# rs485.net
KiCad netlist of a schematic drawn in Altium Designer
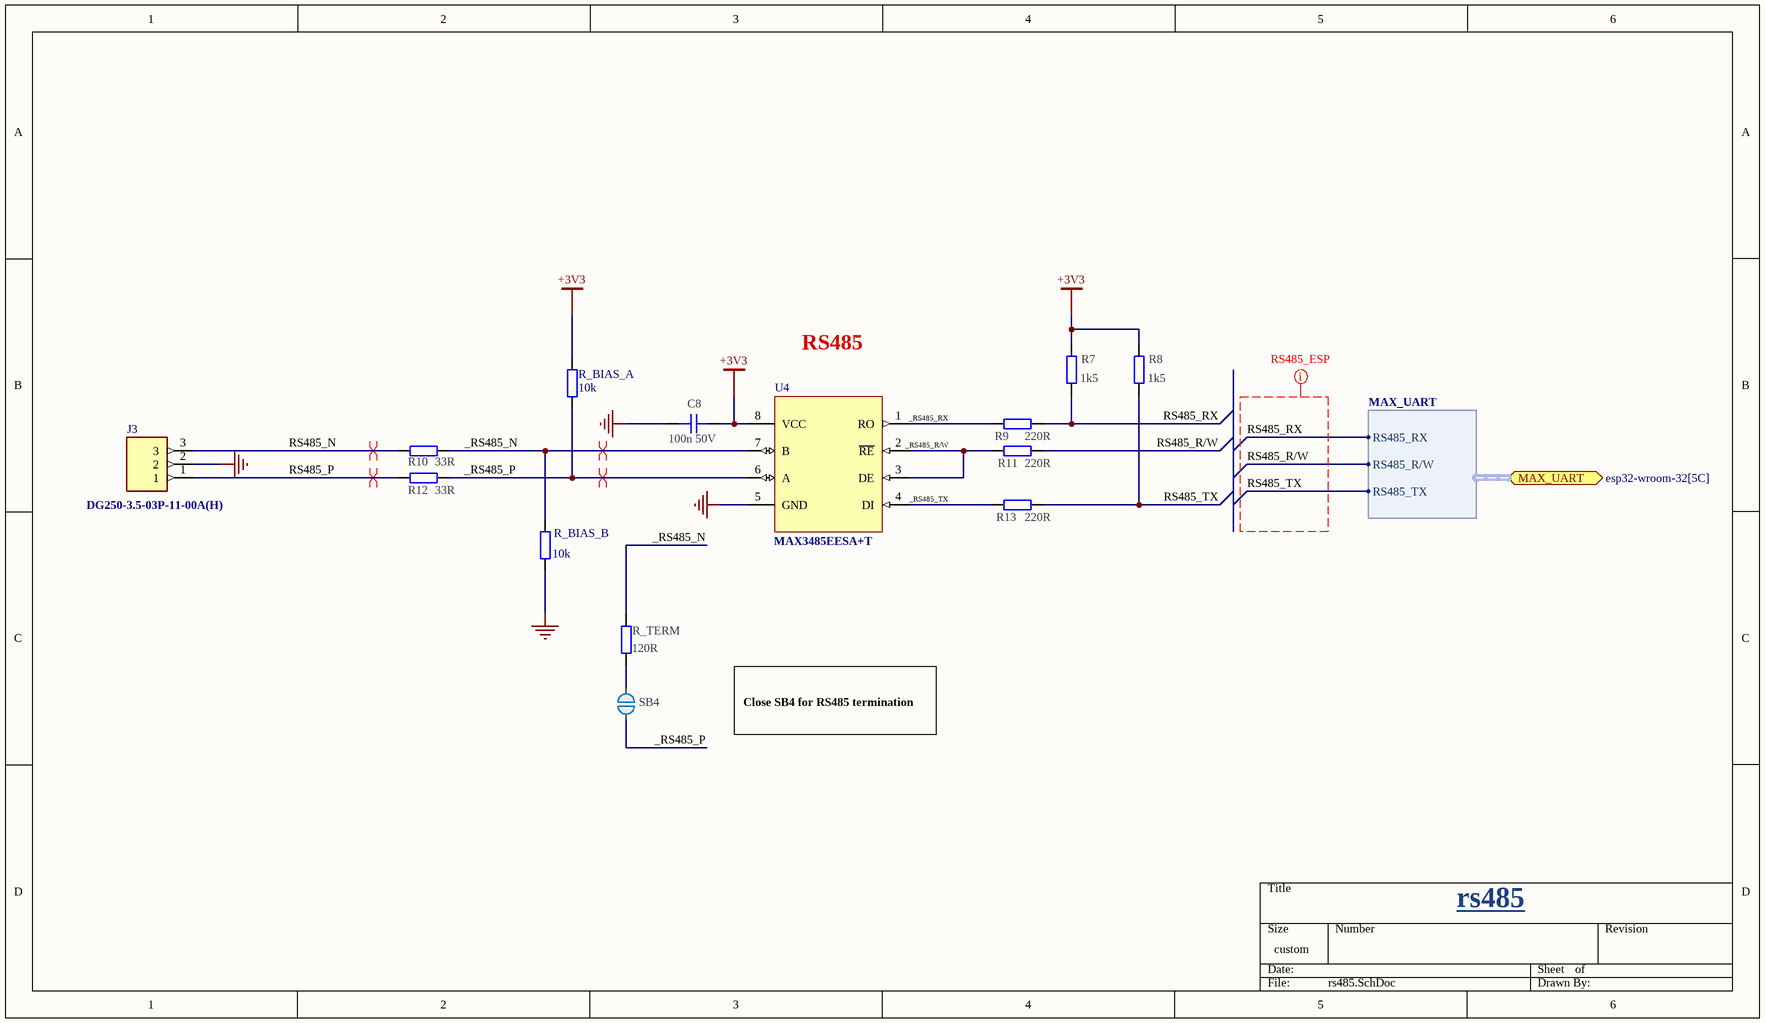
[diagram p0: rs485.SchDoc]

(export (version "E")
  (design (tool "Eeschema 10.0.6"))
  (components
    (comp (ref "C8")
      (value "100n 50V")
      (footprint "CAPC1005X04L")
      (description "Capacitor, X5R, ±20%")
      (fields
        (field (name "PART NUMBER") "C0402-4µ7")
        (field (name "MANUFACTURER") "N.A.")
        (field (name "AUTHOR") "rsk")
      )
      (libsource (lib "Sch_Lib") (part "C0402-4µ7"))
    )
    (comp (ref "J3")
      (value "DG250-3.5-03P-11-00A(H)")
      (footprint "DG250-3.5-03P-11-00AH")
      (description "Terminal block; 3.5mm; with push button; angled 45Â°; ways: 3; 5A")
      (fields (field (name "MF") "Degson"))
      (libsource (lib "Sch_Lib") (part "DG250-3.5-03P-11-00A(H)"))
    )
    (comp (ref "R7")
      (value "1k5")
      (footprint "RESC1005X04L")
      (description "Resistor, ±5%, 0.063W")
      (fields
        (field (name "PART NUMBER") "R0402-0R")
        (field (name "MANUFACTURER") "N.A.")
        (field (name "AUTHOR") "rsk")
      )
      (libsource (lib "Sch_Lib") (part "R0402-0R"))
    )
    (comp (ref "R8")
      (value "1k5")
      (footprint "RESC1005X04L")
      (description "Resistor, ±5%, 0.063W")
      (fields
        (field (name "PART NUMBER") "R0402-0R")
        (field (name "MANUFACTURER") "N.A.")
        (field (name "AUTHOR") "rsk")
      )
      (libsource (lib "Sch_Lib") (part "R0402-0R"))
    )
    (comp (ref "R9")
      (value "220R")
      (footprint "RESC1005X04L")
      (description "Resistor, ±5%, 0.063W")
      (fields
        (field (name "PART NUMBER") "R0402-0R")
        (field (name "MANUFACTURER") "N.A.")
        (field (name "AUTHOR") "rsk")
      )
      (libsource (lib "Sch_Lib") (part "R0402-0R"))
    )
    (comp (ref "R10")
      (value "33R")
      (footprint "RESC1005X04L")
      (description "Resistor, ±5%, 0.063W")
      (fields
        (field (name "PART NUMBER") "R0402-0R")
        (field (name "MANUFACTURER") "N.A.")
        (field (name "AUTHOR") "rsk")
      )
      (libsource (lib "Sch_Lib") (part "R0402-0R"))
    )
    (comp (ref "R11")
      (value "220R")
      (footprint "RESC1005X04L")
      (description "Resistor, ±5%, 0.063W")
      (fields
        (field (name "PART NUMBER") "R0402-0R")
        (field (name "MANUFACTURER") "N.A.")
        (field (name "AUTHOR") "rsk")
      )
      (libsource (lib "Sch_Lib") (part "R0402-0R"))
    )
    (comp (ref "R12")
      (value "33R")
      (footprint "RESC1005X04L")
      (description "Resistor, ±5%, 0.063W")
      (fields
        (field (name "PART NUMBER") "R0402-0R")
        (field (name "MANUFACTURER") "N.A.")
        (field (name "AUTHOR") "rsk")
      )
      (libsource (lib "Sch_Lib") (part "R0402-0R"))
    )
    (comp (ref "R13")
      (value "220R")
      (footprint "RESC1005X04L")
      (description "Resistor, ±5%, 0.063W")
      (fields
        (field (name "PART NUMBER") "R0402-0R")
        (field (name "MANUFACTURER") "N.A.")
        (field (name "AUTHOR") "rsk")
      )
      (libsource (lib "Sch_Lib") (part "R0402-0R"))
    )
    (comp (ref "R_BIAS_A")
      (value "10k")
      (footprint "RES_0603")
      (description "Resistor SMD 0603")
      (libsource (lib "Sch_Lib") (part "RES_0603"))
    )
    (comp (ref "R_BIAS_B")
      (value "10k")
      (footprint "RES_0603")
      (description "Resistor SMD 0603")
      (libsource (lib "Sch_Lib") (part "RES_0603"))
    )
    (comp (ref "R_TERM")
      (value "120R")
      (footprint "RESC1005X04L")
      (description "Resistor, ±5%, 0.063W")
      (fields
        (field (name "PART NUMBER") "R0402-0R")
        (field (name "MANUFACTURER") "N.A.")
        (field (name "AUTHOR") "rsk")
      )
      (libsource (lib "Sch_Lib") (part "R0402-0R"))
    )
    (comp (ref "SB4")
      (value "Solderbridge")
      (footprint "Solderbridge")
      (fields (field (name "MANUFACTURER") "N.A.") (field (name "AUTHOR") "rsk"))
      (libsource (lib "Sch_Lib") (part "Solderbridge"))
    )
    (comp (ref "U4")
      (value "MAX3485EESA+T")
      (footprint "SOIC127P600X175-8N")
      (fields (field (name "MF") "Analog Devices"))
      (libsource (lib "Sch_Lib") (part "MAX3485EESA+T"))
    )
  )
  (nets
    (net (code "2") (name "+3V3") (class "Default")
      (node (ref "C8") (pin "2") (pinfunction "2_2") (pintype "passive"))
      (node (ref "R7") (pin "1") (pinfunction "1_1") (pintype "passive"))
      (node (ref "R8") (pin "1") (pinfunction "1_1") (pintype "passive"))
      (node (ref "R_BIAS_A") (pin "2") (pinfunction "2_2") (pintype "passive"))
      (node (ref "U4") (pin "8") (pinfunction "VCC_8") (pintype "power_in"))
    )
    (net (code "3") (name "/RS485_N") (class "Default")
      (node (ref "J3") (pin "3") (pinfunction "3_3") (pintype "output"))
      (node (ref "R10") (pin "1") (pinfunction "1_1") (pintype "passive"))
    )
    (net (code "4") (name "/RS485_P") (class "Default")
      (node (ref "J3") (pin "1") (pinfunction "1_1") (pintype "output"))
      (node (ref "R12") (pin "1") (pinfunction "1_1") (pintype "passive"))
    )
    (net (code "5") (name "/RS485_RX") (class "Default")
      (node (ref "R7") (pin "2") (pinfunction "2_2") (pintype "passive"))
      (node (ref "R9") (pin "2") (pinfunction "2_2") (pintype "passive"))
    )
    (net (code "6") (name "/RS485_R{slash}W") (class "Default")
      (node (ref "R11") (pin "2") (pinfunction "2_2") (pintype "passive"))
    )
    (net (code "7") (name "/RS485_TX") (class "Default")
      (node (ref "R13") (pin "2") (pinfunction "2_2") (pintype "passive"))
      (node (ref "R8") (pin "2") (pinfunction "2_2") (pintype "passive"))
    )
    (net (code "8") (name "/_RS485_N") (class "Default")
      (node (ref "R10") (pin "2") (pinfunction "2_2") (pintype "passive"))
      (node (ref "R_BIAS_B") (pin "2") (pinfunction "2_2") (pintype "passive"))
      (node (ref "R_TERM") (pin "2") (pinfunction "2_2") (pintype "passive"))
      (node (ref "U4") (pin "7") (pinfunction "B_7") (pintype "bidirectional"))
    )
    (net (code "9") (name "/_RS485_P") (class "Default")
      (node (ref "R12") (pin "2") (pinfunction "2_2") (pintype "passive"))
      (node (ref "R_BIAS_A") (pin "1") (pinfunction "1_1") (pintype "passive"))
      (node (ref "SB4") (pin "2") (pinfunction "1_2") (pintype "passive"))
      (node (ref "U4") (pin "6") (pinfunction "A_6") (pintype "bidirectional"))
    )
    (net (code "10") (name "/_RS485_RX") (class "Default")
      (node (ref "R9") (pin "1") (pinfunction "1_1") (pintype "passive"))
      (node (ref "U4") (pin "1") (pinfunction "RO_1") (pintype "output"))
    )
    (net (code "11") (name "/_RS485_R{slash}W") (class "Default")
      (node (ref "R11") (pin "1") (pinfunction "1_1") (pintype "passive"))
      (node (ref "U4") (pin "2") (pinfunction "~{RE}_2") (pintype "input"))
      (node (ref "U4") (pin "3") (pinfunction "DE_3") (pintype "input"))
    )
    (net (code "12") (name "/_RS485_TX") (class "Default")
      (node (ref "R13") (pin "1") (pinfunction "1_1") (pintype "passive"))
      (node (ref "U4") (pin "4") (pinfunction "DI_4") (pintype "input"))
    )
    (net (code "14") (name "GND") (class "Default")
      (node (ref "C8") (pin "1") (pinfunction "1_1") (pintype "passive"))
      (node (ref "J3") (pin "2") (pinfunction "2_2") (pintype "output"))
      (node (ref "R_BIAS_B") (pin "1") (pinfunction "1_1") (pintype "passive"))
      (node (ref "U4") (pin "5") (pinfunction "GND_5") (pintype "power_in"))
    )
    (net (code "15") (name "Net-(SB4-0)") (class "Default")
      (node (ref "R_TERM") (pin "1") (pinfunction "1_1") (pintype "passive"))
      (node (ref "SB4") (pin "1") (pinfunction "0_1") (pintype "passive"))
    )
  )
)
